# ProPrj_STM32____2024-12-15_1.net
KiCad netlist of a schematic drawn in EasyEDA Pro
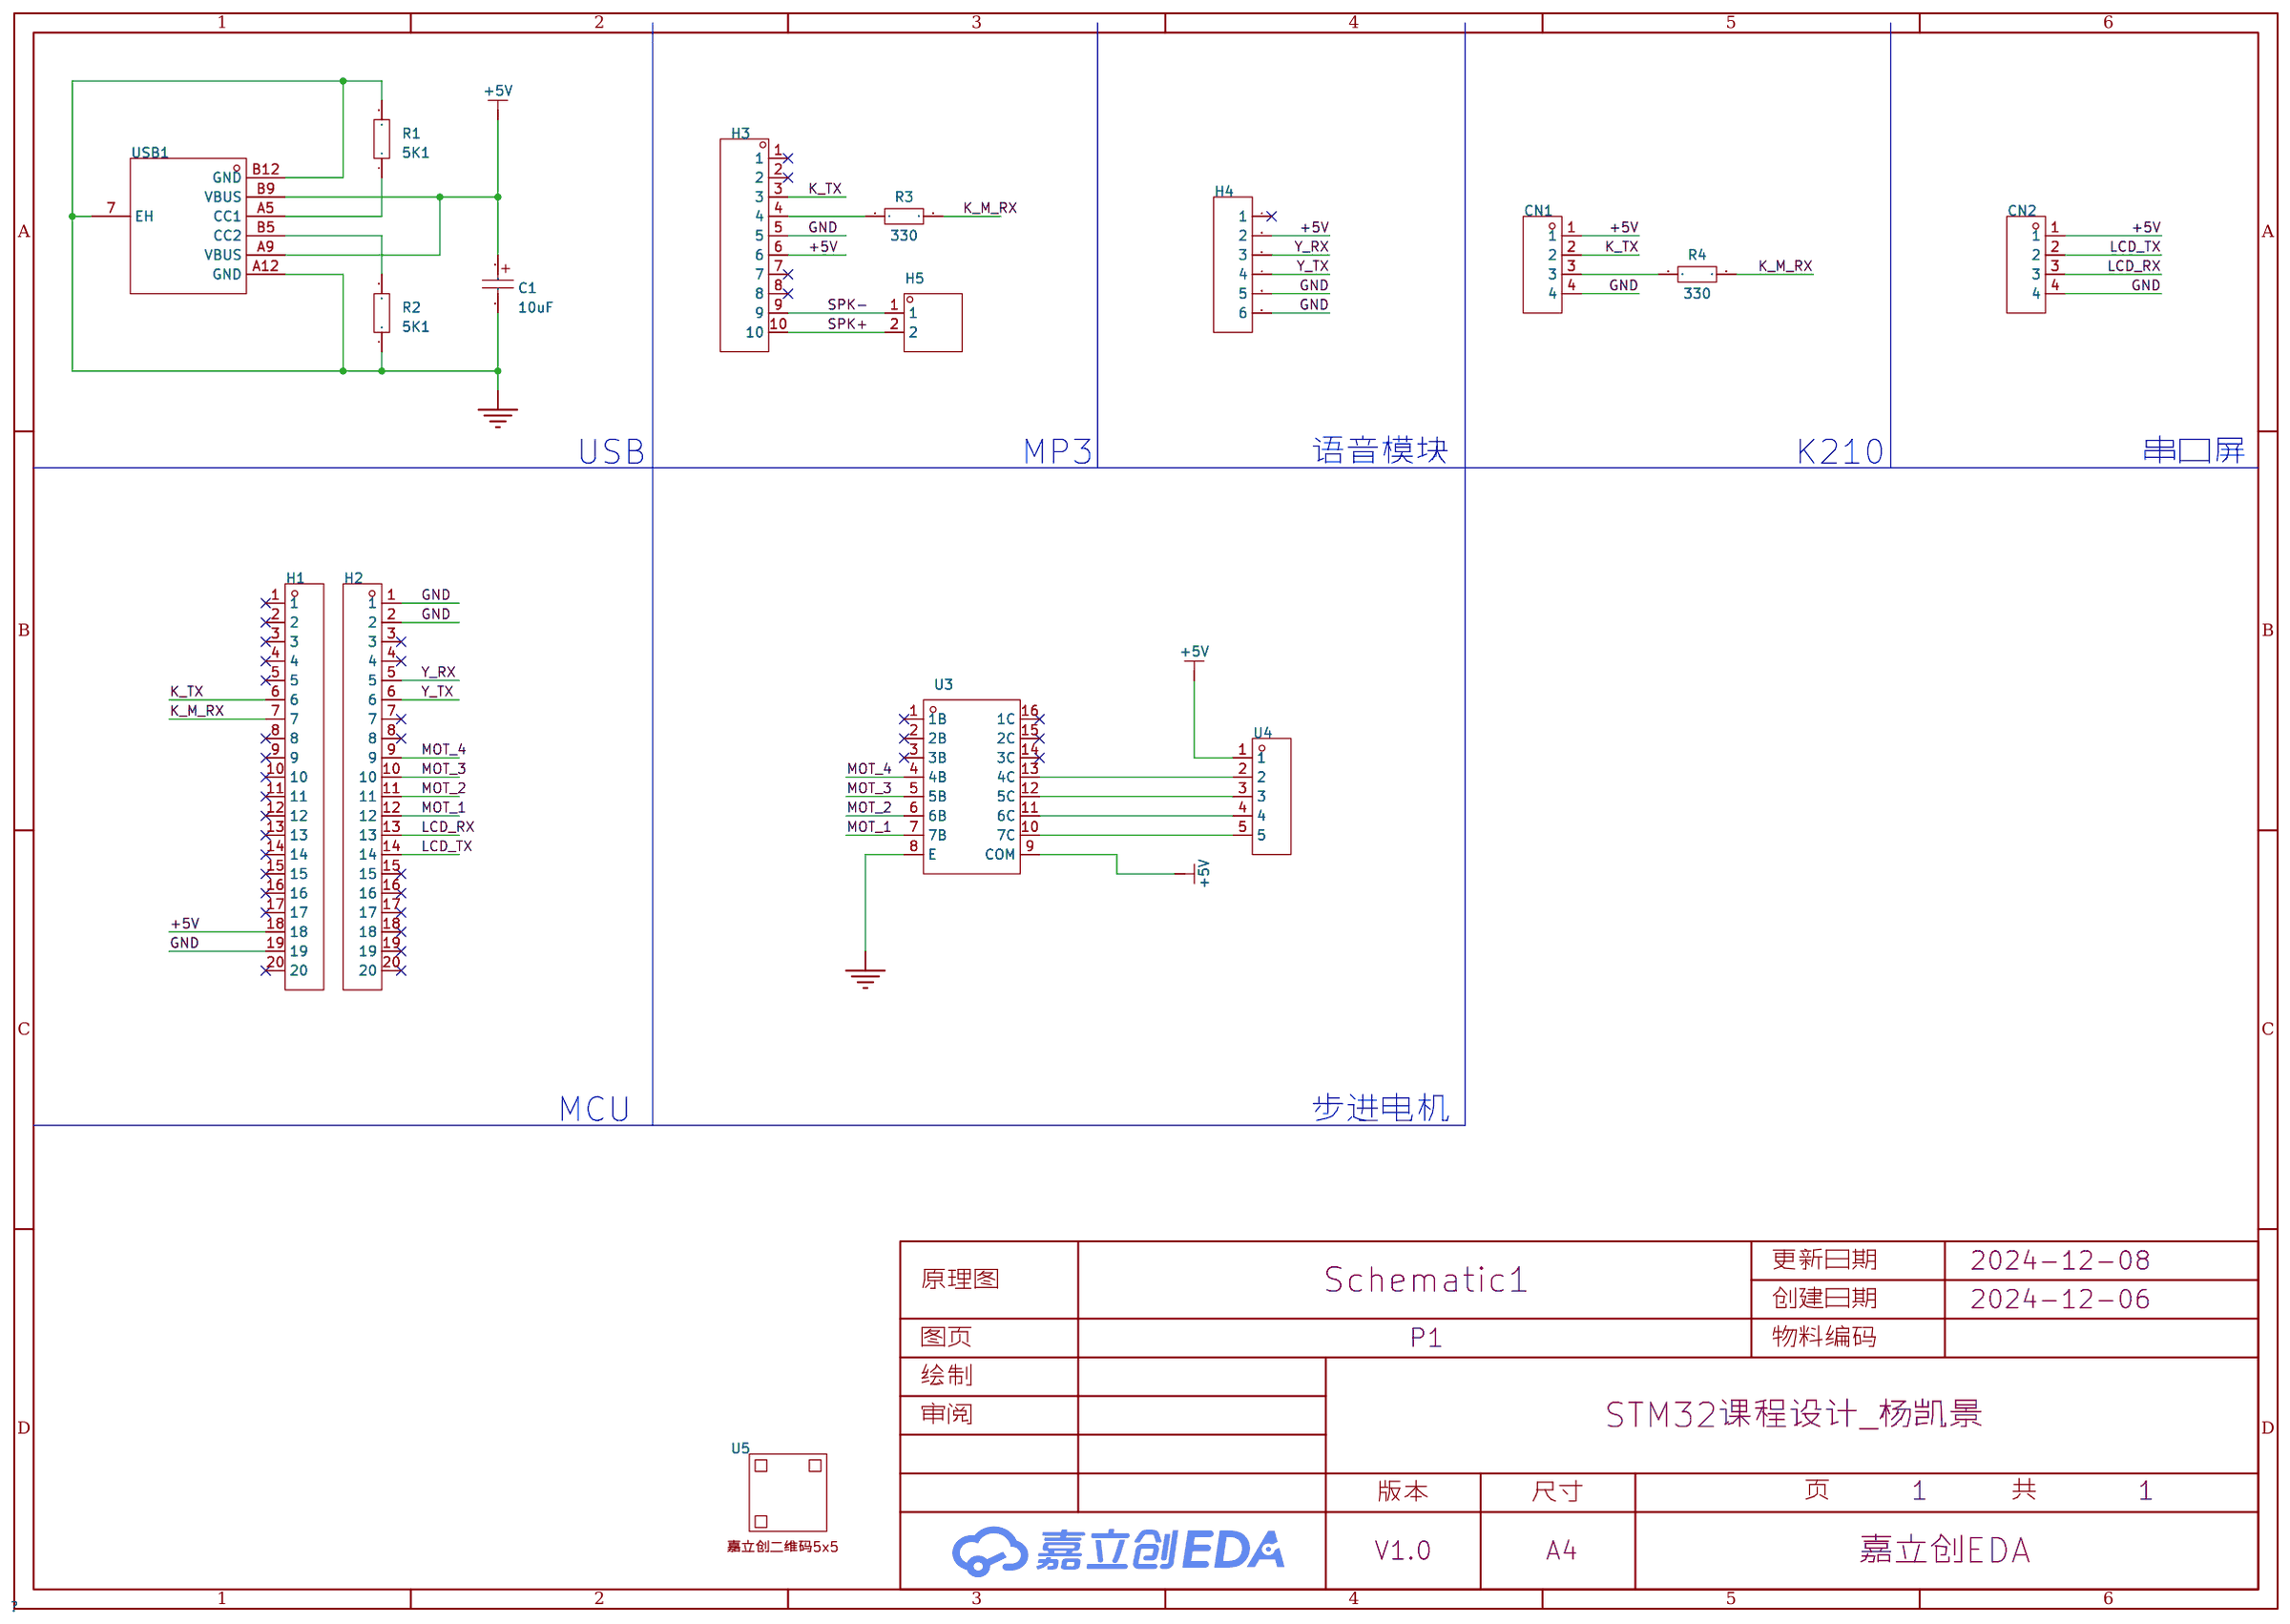
[diagram p0: schematic sheet]

(export (version "E")
  (design (tool "Eeschema 10.0.6"))
  (components
    (comp (ref "C1")
      (value "10uF")
      (footprint "easyedapro:C_Ele_SMD_5x5.4mm")
      (libsource (lib "easyedapro") (part "CAP"))
    )
    (comp (ref "CN1")
      (value "ZX-XH2.54-4PZZ")
      (footprint "easyedapro:CONN-TH_4P-P2.50_4PIN")
      (fields (field (name "Manufacturer") "Megastar(兆星)"))
      (libsource (lib "easyedapro") (part "ZX-XH2.54-4PZZ"))
    )
    (comp (ref "CN2")
      (value "ZX-XH2.54-4PZZ")
      (footprint "easyedapro:CONN-TH_4P-P2.50_4PIN")
      (fields (field (name "Manufacturer") "Megastar(兆星)"))
      (libsource (lib "easyedapro") (part "ZX-XH2.54-4PZZ"))
    )
    (comp (ref "H1")
      (value "~")
      (footprint "easyedapro:HDR-TH_20P-P2.54-V-M-1")
      (libsource (lib "easyedapro") (part "HDR_2.54-1x20P"))
    )
    (comp (ref "H2")
      (value "~")
      (footprint "easyedapro:HDR-TH_20P-P2.54-V-M-1")
      (libsource (lib "easyedapro") (part "HDR_2.54-1x20P"))
    )
    (comp (ref "H3")
      (value "~")
      (footprint "easyedapro:HDR-TH_10P-P2.54-V-M-1")
      (libsource (lib "easyedapro") (part "Header-Male-2.54_1x10"))
    )
    (comp (ref "H4")
      (value "~")
      (footprint "easyedapro:HDR-TH_6P-P2.54-V-M-1")
      (libsource (lib "easyedapro") (part "Header-Male-2.54_1x6"))
    )
    (comp (ref "H5")
      (value "~")
      (footprint "easyedapro:HDR-TH_2P-P2.54-V-M-1")
      (libsource (lib "easyedapro") (part "210S-1*2P L=11.6MMGold-plated black"))
    )
    (comp (ref "R1") (value "5K1") (footprint "easyedapro:R0603") (libsource (lib "easyedapro") (part "电阻")))
    (comp (ref "R2") (value "5K1") (footprint "easyedapro:R0603") (libsource (lib "easyedapro") (part "电阻")))
    (comp (ref "R3") (value "330") (footprint "easyedapro:R0603") (libsource (lib "easyedapro") (part "电阻")))
    (comp (ref "R4") (value "330") (footprint "easyedapro:R0603") (libsource (lib "easyedapro") (part "电阻")))
    (comp (ref "U3")
      (value "ULN2003AN(XBLW)")
      (footprint "easyedapro:PDIP-16_L19.3-W6.4-P2.54-LS7.9-BL")
      (description "通道数:七路;集射击穿电压(Vceo):50V;集电极电流(Ic):500mA;")
      (fields (field (name "Manufacturer") "XBLW(芯伯乐)"))
      (libsource (lib "easyedapro") (part "ULN2003AN(XBLW)"))
    )
    (comp (ref "U4")
      (value "ZX-XH2.54-5PZZ")
      (footprint "easyedapro:CONN-TH_5P-P2.50_ZX-XH2.54-5PZZ")
      (fields (field (name "Manufacturer") "Megastar(兆星)"))
      (libsource (lib "easyedapro") (part "ZX-XH2.54-5PZZ"))
    )
    (comp (ref "U5")
      (value "~")
      (footprint "easyedapro:JLC-QRCODE-5x5")
      (libsource (lib "easyedapro") (part "嘉立创二维码5x5"))
    )
    (comp (ref "USB1")
      (value "TYPE-C 6P(073)")
      (footprint "easyedapro:TYPE-C-SMD_TYPE-C-6P_5")
      (description "连接器类型:Type-C;标准:USB 3.1;公母:母;安装方式:卧贴;触点数量:6P;端口数量:1;额定电流 - 电源:3A;工作温度范围:-25°C~+85°C;")
      (fields (field (name "Manufacturer") "SHOU HAN(首韩)"))
      (libsource (lib "easyedapro") (part "TYPE-C 6P(073)"))
    )
  )
  (nets
    (net (code "1") (name "+5V") (class "Default")
      (node (ref "C1") (pin "1") (pinfunction "1_1") (pintype "input"))
      (node (ref "CN1") (pin "1") (pinfunction "1_1") (pintype "unspecified"))
      (node (ref "CN2") (pin "1") (pinfunction "1_1") (pintype "unspecified"))
      (node (ref "H1") (pin "18") (pinfunction "18_18") (pintype "input"))
      (node (ref "H3") (pin "6") (pinfunction "6_6") (pintype "unspecified"))
      (node (ref "H4") (pin "2") (pinfunction "2_2") (pintype "input"))
      (node (ref "U3") (pin "9") (pinfunction "COM_9") (pintype "unspecified"))
      (node (ref "U4") (pin "1") (pinfunction "1_1") (pintype "unspecified"))
      (node (ref "USB1") (pin "A9") (pinfunction "VBUS_A9") (pintype "unspecified"))
      (node (ref "USB1") (pin "B9") (pinfunction "VBUS_B9") (pintype "unspecified"))
    )
    (net (code "2") (name "/K_M_RX") (class "Default")
      (node (ref "H1") (pin "7") (pinfunction "7_7") (pintype "input"))
      (node (ref "R3") (pin "2") (pinfunction "2_2") (pintype "input"))
      (node (ref "R4") (pin "2") (pinfunction "2_2") (pintype "input"))
    )
    (net (code "3") (name "/K_TX") (class "Default")
      (node (ref "CN1") (pin "2") (pinfunction "2_2") (pintype "unspecified"))
      (node (ref "H1") (pin "6") (pinfunction "6_6") (pintype "input"))
      (node (ref "H3") (pin "3") (pinfunction "3_3") (pintype "unspecified"))
    )
    (net (code "4") (name "/LCD_RX") (class "Default")
      (node (ref "CN2") (pin "3") (pinfunction "3_3") (pintype "unspecified"))
      (node (ref "H2") (pin "13") (pinfunction "13_13") (pintype "input"))
    )
    (net (code "5") (name "/LCD_TX") (class "Default")
      (node (ref "CN2") (pin "2") (pinfunction "2_2") (pintype "unspecified"))
      (node (ref "H2") (pin "14") (pinfunction "14_14") (pintype "input"))
    )
    (net (code "6") (name "/MOT_1") (class "Default")
      (node (ref "H2") (pin "12") (pinfunction "12_12") (pintype "input"))
      (node (ref "U3") (pin "7") (pinfunction "7B_7") (pintype "unspecified"))
    )
    (net (code "7") (name "/MOT_2") (class "Default")
      (node (ref "H2") (pin "11") (pinfunction "11_11") (pintype "input"))
      (node (ref "U3") (pin "6") (pinfunction "6B_6") (pintype "unspecified"))
    )
    (net (code "8") (name "/MOT_3") (class "Default")
      (node (ref "H2") (pin "10") (pinfunction "10_10") (pintype "input"))
      (node (ref "U3") (pin "5") (pinfunction "5B_5") (pintype "unspecified"))
    )
    (net (code "9") (name "/MOT_4") (class "Default")
      (node (ref "H2") (pin "9") (pinfunction "9_9") (pintype "input"))
      (node (ref "U3") (pin "4") (pinfunction "4B_4") (pintype "unspecified"))
    )
    (net (code "10") (name "/SPK+") (class "Default")
      (node (ref "H3") (pin "10") (pinfunction "10_10") (pintype "unspecified"))
      (node (ref "H5") (pin "2") (pinfunction "2_2") (pintype "unspecified"))
    )
    (net (code "11") (name "/SPK-") (class "Default")
      (node (ref "H3") (pin "9") (pinfunction "9_9") (pintype "unspecified"))
      (node (ref "H5") (pin "1") (pinfunction "1_1") (pintype "unspecified"))
    )
    (net (code "12") (name "/Y_RX") (class "Default")
      (node (ref "H2") (pin "5") (pinfunction "5_5") (pintype "input"))
      (node (ref "H4") (pin "3") (pinfunction "3_3") (pintype "input"))
    )
    (net (code "13") (name "/Y_TX") (class "Default")
      (node (ref "H2") (pin "6") (pinfunction "6_6") (pintype "input"))
      (node (ref "H4") (pin "4") (pinfunction "4_4") (pintype "input"))
    )
    (net (code "14") (name "GND") (class "Default")
      (node (ref "C1") (pin "2") (pinfunction "2_2") (pintype "input"))
      (node (ref "CN1") (pin "4") (pinfunction "4_4") (pintype "unspecified"))
      (node (ref "CN2") (pin "4") (pinfunction "4_4") (pintype "unspecified"))
      (node (ref "H1") (pin "19") (pinfunction "19_19") (pintype "input"))
      (node (ref "H2") (pin "1") (pinfunction "1_1") (pintype "input"))
      (node (ref "H2") (pin "2") (pinfunction "2_2") (pintype "input"))
      (node (ref "H3") (pin "5") (pinfunction "5_5") (pintype "unspecified"))
      (node (ref "H4") (pin "5") (pinfunction "5_5") (pintype "input"))
      (node (ref "H4") (pin "6") (pinfunction "6_6") (pintype "input"))
      (node (ref "R1") (pin "2") (pinfunction "2_2") (pintype "input"))
      (node (ref "R2") (pin "1") (pinfunction "1_1") (pintype "input"))
      (node (ref "U3") (pin "8") (pinfunction "E_8") (pintype "unspecified"))
      (node (ref "USB1") (pin "7") (pinfunction "EH_7") (pintype "unspecified"))
      (node (ref "USB1") (pin "A12") (pinfunction "GND_A12") (pintype "unspecified"))
      (node (ref "USB1") (pin "B12") (pinfunction "GND_B12") (pintype "unspecified"))
    )
    (net (code "15") (name "Net-(CN1-Pad3)") (class "Default")
      (node (ref "CN1") (pin "3") (pinfunction "3_3") (pintype "unspecified"))
      (node (ref "R4") (pin "1") (pinfunction "1_1") (pintype "input"))
    )
    (net (code "16") (name "Net-(H3-Pad4)") (class "Default")
      (node (ref "H3") (pin "4") (pinfunction "4_4") (pintype "unspecified"))
      (node (ref "R3") (pin "1") (pinfunction "1_1") (pintype "input"))
    )
    (net (code "17") (name "Net-(U3-4C)") (class "Default")
      (node (ref "U3") (pin "13") (pinfunction "4C_13") (pintype "unspecified"))
      (node (ref "U4") (pin "2") (pinfunction "2_2") (pintype "unspecified"))
    )
    (net (code "18") (name "Net-(U3-5C)") (class "Default")
      (node (ref "U3") (pin "12") (pinfunction "5C_12") (pintype "unspecified"))
      (node (ref "U4") (pin "3") (pinfunction "3_3") (pintype "unspecified"))
    )
    (net (code "19") (name "Net-(U3-6C)") (class "Default")
      (node (ref "U3") (pin "11") (pinfunction "6C_11") (pintype "unspecified"))
      (node (ref "U4") (pin "4") (pinfunction "4_4") (pintype "unspecified"))
    )
    (net (code "20") (name "Net-(U3-7C)") (class "Default")
      (node (ref "U3") (pin "10") (pinfunction "7C_10") (pintype "unspecified"))
      (node (ref "U4") (pin "5") (pinfunction "5_5") (pintype "unspecified"))
    )
    (net (code "21") (name "Net-(USB1-CC1)") (class "Default")
      (node (ref "R1") (pin "1") (pinfunction "1_1") (pintype "input"))
      (node (ref "USB1") (pin "A5") (pinfunction "CC1_A5") (pintype "unspecified"))
    )
    (net (code "22") (name "Net-(USB1-CC2)") (class "Default")
      (node (ref "R2") (pin "2") (pinfunction "2_2") (pintype "input"))
      (node (ref "USB1") (pin "B5") (pinfunction "CC2_B5") (pintype "unspecified"))
    )
    (net (code "23") (name "unconnected-(H1-Pad1)") (class "Default")
      (node (ref "H1") (pin "1") (pinfunction "1_1") (pintype "input+no_connect"))
    )
    (net (code "24") (name "unconnected-(H1-Pad2)") (class "Default")
      (node (ref "H1") (pin "2") (pinfunction "2_2") (pintype "input+no_connect"))
    )
    (net (code "25") (name "unconnected-(H1-Pad3)") (class "Default")
      (node (ref "H1") (pin "3") (pinfunction "3_3") (pintype "input+no_connect"))
    )
    (net (code "26") (name "unconnected-(H1-Pad4)") (class "Default")
      (node (ref "H1") (pin "4") (pinfunction "4_4") (pintype "input+no_connect"))
    )
    (net (code "27") (name "unconnected-(H1-Pad5)") (class "Default")
      (node (ref "H1") (pin "5") (pinfunction "5_5") (pintype "input+no_connect"))
    )
    (net (code "28") (name "unconnected-(H1-Pad8)") (class "Default")
      (node (ref "H1") (pin "8") (pinfunction "8_8") (pintype "input+no_connect"))
    )
    (net (code "29") (name "unconnected-(H1-Pad9)") (class "Default")
      (node (ref "H1") (pin "9") (pinfunction "9_9") (pintype "input+no_connect"))
    )
    (net (code "30") (name "unconnected-(H1-Pad10)") (class "Default")
      (node (ref "H1") (pin "10") (pinfunction "10_10") (pintype "input+no_connect"))
    )
    (net (code "31") (name "unconnected-(H1-Pad11)") (class "Default")
      (node (ref "H1") (pin "11") (pinfunction "11_11") (pintype "input+no_connect"))
    )
    (net (code "32") (name "unconnected-(H1-Pad12)") (class "Default")
      (node (ref "H1") (pin "12") (pinfunction "12_12") (pintype "input+no_connect"))
    )
    (net (code "33") (name "unconnected-(H1-Pad13)") (class "Default")
      (node (ref "H1") (pin "13") (pinfunction "13_13") (pintype "input+no_connect"))
    )
    (net (code "34") (name "unconnected-(H1-Pad14)") (class "Default")
      (node (ref "H1") (pin "14") (pinfunction "14_14") (pintype "input+no_connect"))
    )
    (net (code "35") (name "unconnected-(H1-Pad15)") (class "Default")
      (node (ref "H1") (pin "15") (pinfunction "15_15") (pintype "input+no_connect"))
    )
    (net (code "36") (name "unconnected-(H1-Pad16)") (class "Default")
      (node (ref "H1") (pin "16") (pinfunction "16_16") (pintype "input+no_connect"))
    )
    (net (code "37") (name "unconnected-(H1-Pad17)") (class "Default")
      (node (ref "H1") (pin "17") (pinfunction "17_17") (pintype "input+no_connect"))
    )
    (net (code "38") (name "unconnected-(H1-Pad20)") (class "Default")
      (node (ref "H1") (pin "20") (pinfunction "20_20") (pintype "input+no_connect"))
    )
    (net (code "39") (name "unconnected-(H2-Pad3)") (class "Default")
      (node (ref "H2") (pin "3") (pinfunction "3_3") (pintype "input+no_connect"))
    )
    (net (code "40") (name "unconnected-(H2-Pad4)") (class "Default")
      (node (ref "H2") (pin "4") (pinfunction "4_4") (pintype "input+no_connect"))
    )
    (net (code "41") (name "unconnected-(H2-Pad7)") (class "Default")
      (node (ref "H2") (pin "7") (pinfunction "7_7") (pintype "input+no_connect"))
    )
    (net (code "42") (name "unconnected-(H2-Pad8)") (class "Default")
      (node (ref "H2") (pin "8") (pinfunction "8_8") (pintype "input+no_connect"))
    )
    (net (code "43") (name "unconnected-(H2-Pad15)") (class "Default")
      (node (ref "H2") (pin "15") (pinfunction "15_15") (pintype "input+no_connect"))
    )
    (net (code "44") (name "unconnected-(H2-Pad16)") (class "Default")
      (node (ref "H2") (pin "16") (pinfunction "16_16") (pintype "input+no_connect"))
    )
    (net (code "45") (name "unconnected-(H2-Pad17)") (class "Default")
      (node (ref "H2") (pin "17") (pinfunction "17_17") (pintype "input+no_connect"))
    )
    (net (code "46") (name "unconnected-(H2-Pad18)") (class "Default")
      (node (ref "H2") (pin "18") (pinfunction "18_18") (pintype "input+no_connect"))
    )
    (net (code "47") (name "unconnected-(H2-Pad19)") (class "Default")
      (node (ref "H2") (pin "19") (pinfunction "19_19") (pintype "input+no_connect"))
    )
    (net (code "48") (name "unconnected-(H2-Pad20)") (class "Default")
      (node (ref "H2") (pin "20") (pinfunction "20_20") (pintype "input+no_connect"))
    )
    (net (code "49") (name "unconnected-(H3-Pad1)") (class "Default")
      (node (ref "H3") (pin "1") (pinfunction "1_1") (pintype "unspecified+no_connect"))
    )
    (net (code "50") (name "unconnected-(H3-Pad2)") (class "Default")
      (node (ref "H3") (pin "2") (pinfunction "2_2") (pintype "unspecified+no_connect"))
    )
    (net (code "51") (name "unconnected-(H3-Pad7)") (class "Default")
      (node (ref "H3") (pin "7") (pinfunction "7_7") (pintype "unspecified+no_connect"))
    )
    (net (code "52") (name "unconnected-(H3-Pad8)") (class "Default")
      (node (ref "H3") (pin "8") (pinfunction "8_8") (pintype "unspecified+no_connect"))
    )
    (net (code "53") (name "unconnected-(H4-Pad1)") (class "Default")
      (node (ref "H4") (pin "1") (pinfunction "1_1") (pintype "input+no_connect"))
    )
    (net (code "54") (name "unconnected-(U3-1B-Pad1)") (class "Default")
      (node (ref "U3") (pin "1") (pinfunction "1B_1") (pintype "unspecified+no_connect"))
    )
    (net (code "55") (name "unconnected-(U3-1C-Pad16)") (class "Default")
      (node (ref "U3") (pin "16") (pinfunction "1C_16") (pintype "unspecified+no_connect"))
    )
    (net (code "56") (name "unconnected-(U3-2B-Pad2)") (class "Default")
      (node (ref "U3") (pin "2") (pinfunction "2B_2") (pintype "unspecified+no_connect"))
    )
    (net (code "57") (name "unconnected-(U3-2C-Pad15)") (class "Default")
      (node (ref "U3") (pin "15") (pinfunction "2C_15") (pintype "unspecified+no_connect"))
    )
    (net (code "58") (name "unconnected-(U3-3B-Pad3)") (class "Default")
      (node (ref "U3") (pin "3") (pinfunction "3B_3") (pintype "unspecified+no_connect"))
    )
    (net (code "59") (name "unconnected-(U3-3C-Pad14)") (class "Default")
      (node (ref "U3") (pin "14") (pinfunction "3C_14") (pintype "unspecified+no_connect"))
    )
  )
)
